# Earl-Nano-Stepper-Dual.net
KiCad netlist of a schematic drawn in EAGLE
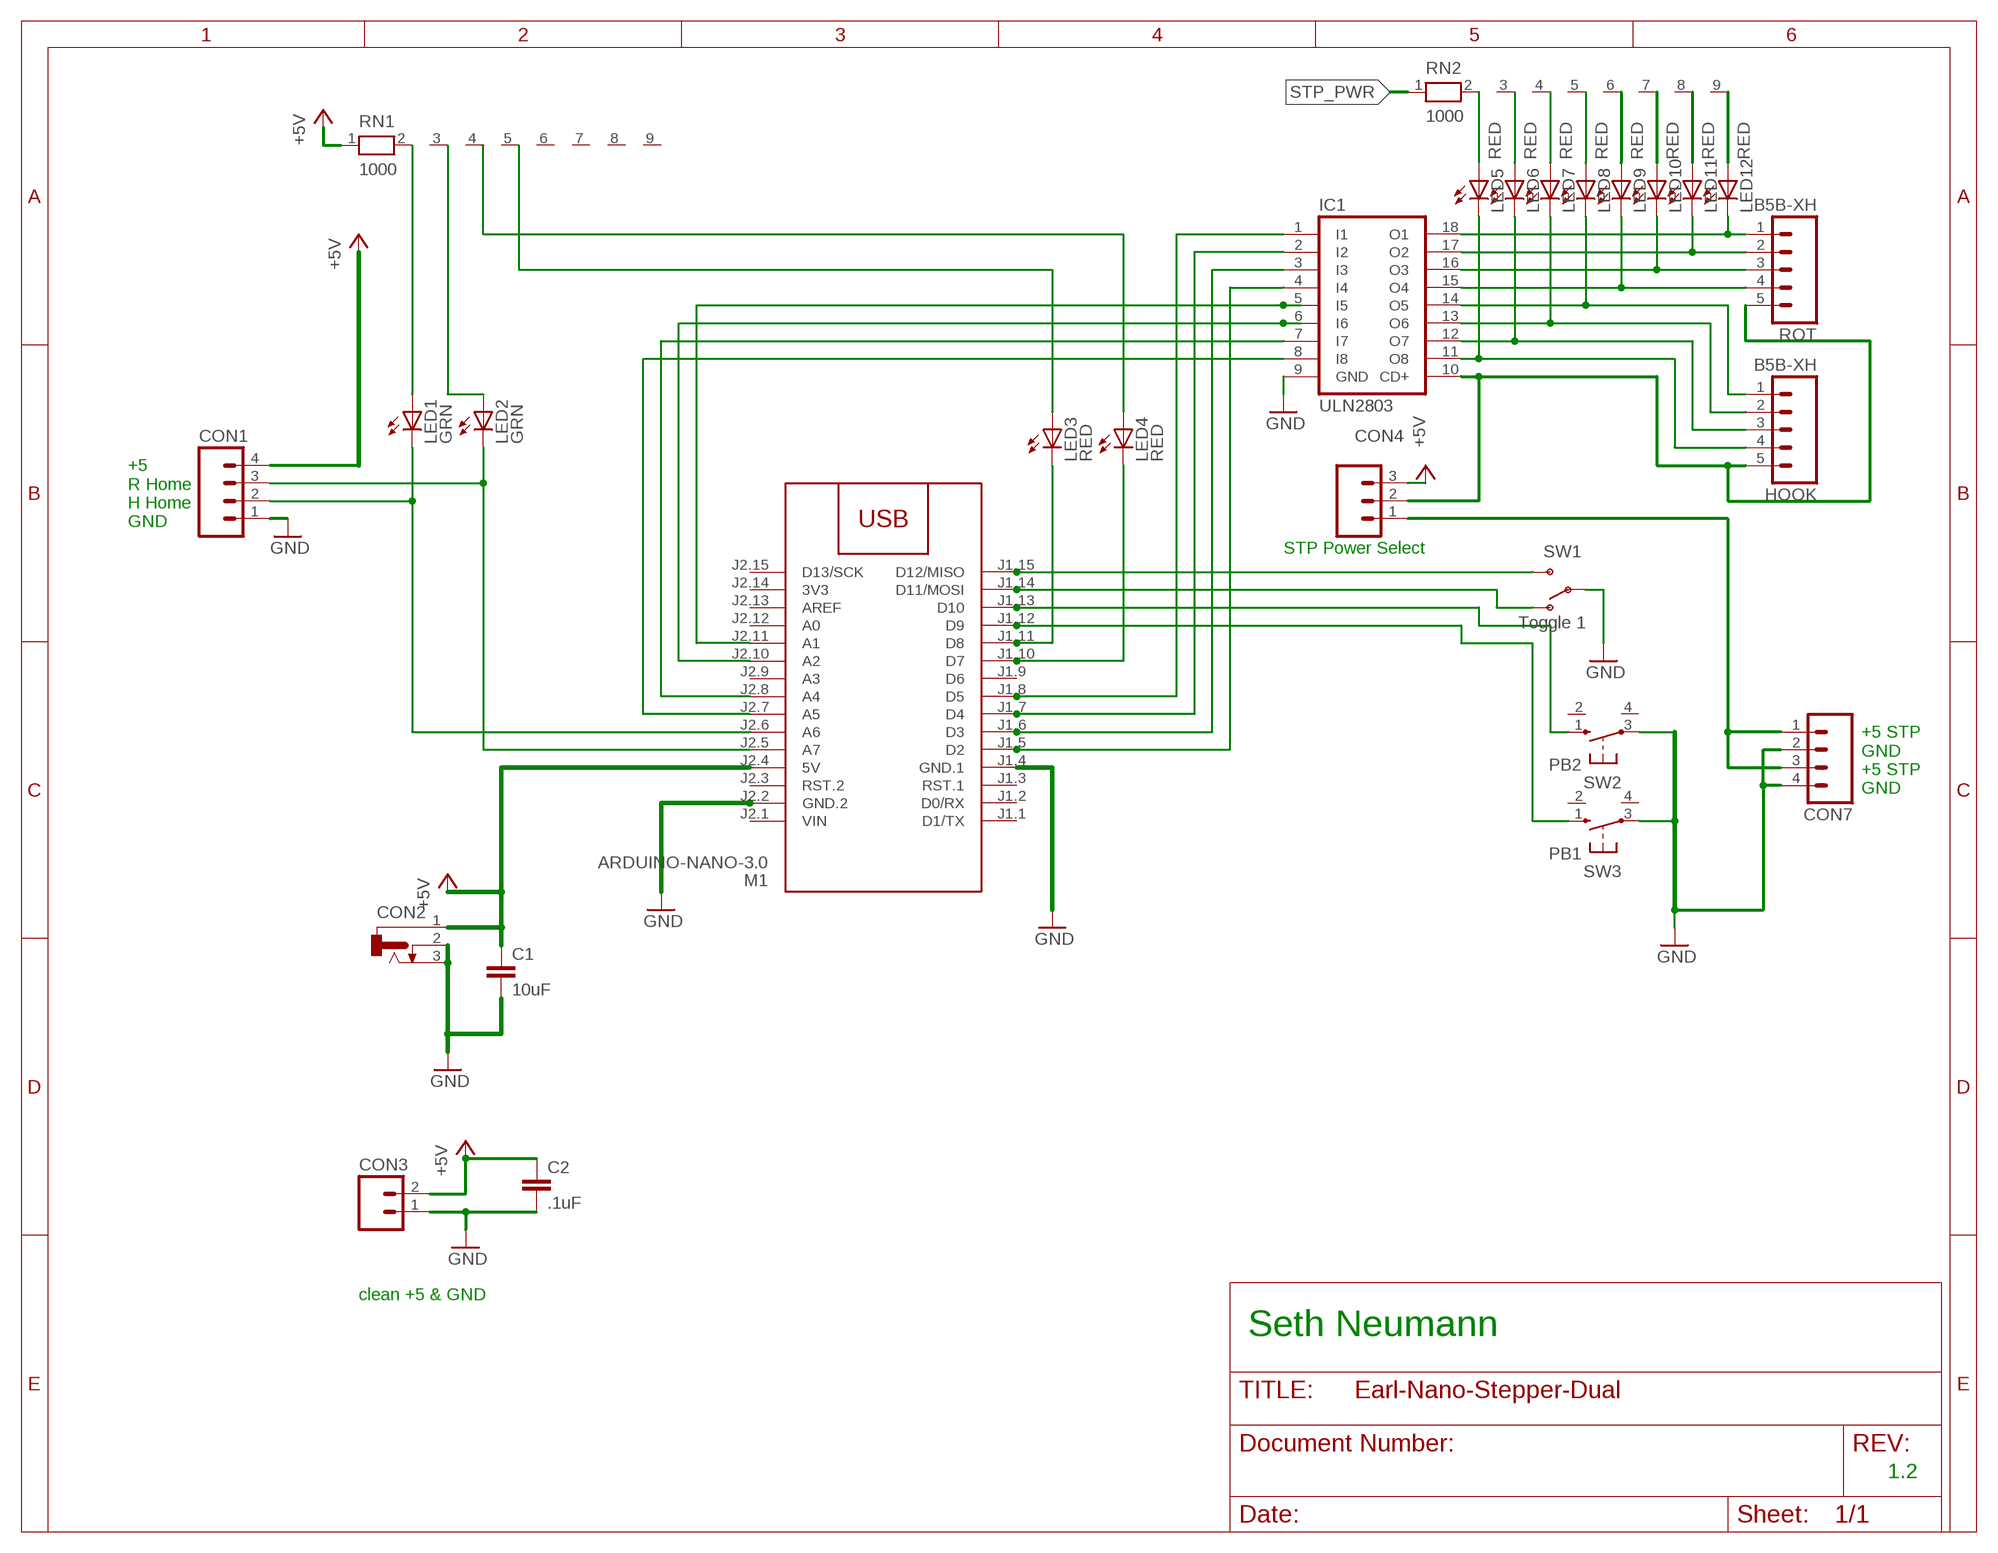
[diagram p0: schematic, sheet 1]

(export (version "E")
  (design (tool "Eeschema 10.0.6"))
  (components
    (comp (ref "C1")
      (value "10uF")
      (footprint "eagle-import:C5B3")
      (libsource (lib "eagle-import") (part "C5/3"))
    )
    (comp (ref "C2")
      (value ".1uF")
      (footprint "eagle-import:C5B3")
      (libsource (lib "eagle-import") (part "C5/3"))
    )
    (comp (ref "CON1")
      (value "CONNECTOR-M04LOCK")
      (footprint "eagle-import:1X04_LOCK")
      (libsource (lib "eagle-import") (part "CONNECTOR-M04LOCK"))
    )
    (comp (ref "CON2")
      (value "CONNECTOR-DC-POWER-RA")
      (footprint "eagle-import:DCJ0202")
      (libsource (lib "eagle-import") (part "CONNECTOR-DC-POWER-RA"))
    )
    (comp (ref "CON3")
      (value "CONNECTOR-M02350-LOCK")
      (footprint "eagle-import:1751248")
      (libsource (lib "eagle-import") (part "CONNECTOR-M02350-LOCK"))
    )
    (comp (ref "CON4")
      (value "CONNECTOR-M03254-LOCK")
      (footprint "eagle-import:3POL254")
      (libsource (lib "eagle-import") (part "CONNECTOR-M03254-LOCK"))
    )
    (comp (ref "CON7")
      (value "CONNECTOR-M04SCREW_LOCK")
      (footprint "eagle-import:SCREWTERMINAL-3.5MM-4_LOCK")
      (libsource (lib "eagle-import") (part "CONNECTOR-M04SCREW_LOCK"))
    )
    (comp (ref "HOOK")
      (value "B5B-XH")
      (footprint "eagle-import:1X05_LOCK")
      (libsource (lib "eagle-import") (part "CONNECTOR-M05LOCK"))
    )
    (comp (ref "IC1")
      (value "ULN2803")
      (footprint "eagle-import:DIL18")
      (libsource (lib "eagle-import") (part "ULN2803A"))
    )
    (comp (ref "LED1")
      (value "GRN")
      (footprint "eagle-import:LED3MM")
      (libsource (lib "eagle-import") (part "LEDLED3MM"))
    )
    (comp (ref "LED2")
      (value "GRN")
      (footprint "eagle-import:LED3MM")
      (libsource (lib "eagle-import") (part "LEDLED3MM"))
    )
    (comp (ref "LED3")
      (value "RED")
      (footprint "eagle-import:LED3MM")
      (libsource (lib "eagle-import") (part "LEDLED3MM"))
    )
    (comp (ref "LED4")
      (value "RED")
      (footprint "eagle-import:LED3MM")
      (libsource (lib "eagle-import") (part "LEDLED3MM"))
    )
    (comp (ref "LED5")
      (value "RED")
      (footprint "eagle-import:LED3MM")
      (libsource (lib "eagle-import") (part "LEDLED3MM"))
    )
    (comp (ref "LED6")
      (value "RED")
      (footprint "eagle-import:LED3MM")
      (libsource (lib "eagle-import") (part "LEDLED3MM"))
    )
    (comp (ref "LED7")
      (value "RED")
      (footprint "eagle-import:LED3MM")
      (libsource (lib "eagle-import") (part "LEDLED3MM"))
    )
    (comp (ref "LED8")
      (value "RED")
      (footprint "eagle-import:LED3MM")
      (libsource (lib "eagle-import") (part "LEDLED3MM"))
    )
    (comp (ref "LED9")
      (value "RED")
      (footprint "eagle-import:LED3MM")
      (libsource (lib "eagle-import") (part "LEDLED3MM"))
    )
    (comp (ref "LED10")
      (value "RED")
      (footprint "eagle-import:LED3MM")
      (libsource (lib "eagle-import") (part "LEDLED3MM"))
    )
    (comp (ref "LED11")
      (value "RED")
      (footprint "eagle-import:LED3MM")
      (libsource (lib "eagle-import") (part "LEDLED3MM"))
    )
    (comp (ref "LED12")
      (value "RED")
      (footprint "eagle-import:LED3MM")
      (libsource (lib "eagle-import") (part "LEDLED3MM"))
    )
    (comp (ref "M1")
      (value "ARDUINO-NANO-3.0")
      (footprint "eagle-import:ARDUINO-NANO-3.0")
      (libsource (lib "eagle-import") (part "ARDUINO-NANO-3.0"))
    )
    (comp (ref "RN1")
      (value "1000")
      (footprint "eagle-import:RN-9")
      (libsource (lib "eagle-import") (part "RN08"))
    )
    (comp (ref "RN2")
      (value "1000")
      (footprint "eagle-import:RN-9")
      (libsource (lib "eagle-import") (part "RN08"))
    )
    (comp (ref "ROT")
      (value "B5B-XH")
      (footprint "eagle-import:1X05_LOCK")
      (libsource (lib "eagle-import") (part "CONNECTOR-M05LOCK"))
    )
    (comp (ref "SW1")
      (value "Toggle 1")
      (footprint "eagle-import:SWITCH-SPDT-508")
      (libsource (lib "eagle-import") (part "SWITCH-SPSTPTH-508"))
    )
    (comp (ref "SW2")
      (value "PB2")
      (footprint "eagle-import:4P-PTH-6.0X6.0X5.0H")
      (libsource (lib "eagle-import") (part "SWITCH-(ON)SMALLPADS"))
    )
    (comp (ref "SW3")
      (value "PB1")
      (footprint "eagle-import:4P-PTH-6.0X6.0X5.0H")
      (libsource (lib "eagle-import") (part "SWITCH-(ON)SMALLPADS"))
    )
  )
  (nets
    (net (code "1") (name "+5V") (class "Default")
      (node (ref "C1") (pin "1") (pinfunction "1_1") (pintype "passive"))
      (node (ref "C2") (pin "1") (pinfunction "1_1") (pintype "passive"))
      (node (ref "CON1") (pin "4") (pinfunction "4_4") (pintype "passive"))
      (node (ref "CON2") (pin "1") (pinfunction "1_1") (pintype "passive"))
      (node (ref "CON3") (pin "2") (pinfunction "B_2") (pintype "passive"))
      (node (ref "CON4") (pin "3") (pinfunction "3_3") (pintype "passive"))
      (node (ref "M1") (pin "J2.4") (pinfunction "5V_J2.4") (pintype "power_in"))
      (node (ref "RN1") (pin "1") (pinfunction "1_1") (pintype "passive"))
    )
    (net (code "2") (name "/3V3") (class "Default")
      (node (ref "M1") (pin "J2.14") (pinfunction "3V3_J2.14") (pintype "power_in"))
    )
    (net (code "3") (name "/VIN") (class "Default")
      (node (ref "M1") (pin "J2.1") (pinfunction "VIN_J2.1") (pintype "power_in"))
    )
    (net (code "4") (name "GND") (class "Default")
      (node (ref "C1") (pin "2") (pinfunction "2_2") (pintype "passive"))
      (node (ref "C2") (pin "2") (pinfunction "2_2") (pintype "passive"))
      (node (ref "CON1") (pin "1") (pinfunction "1_1") (pintype "passive"))
      (node (ref "CON2") (pin "2") (pinfunction "2_2") (pintype "passive"))
      (node (ref "CON2") (pin "3") (pinfunction "3_3") (pintype "passive"))
      (node (ref "CON3") (pin "1") (pinfunction "A_1") (pintype "passive"))
      (node (ref "CON7") (pin "2") (pinfunction "2_2") (pintype "passive"))
      (node (ref "CON7") (pin "4") (pinfunction "4_4") (pintype "passive"))
      (node (ref "IC1") (pin "9") (pinfunction "GND_9") (pintype "power_in"))
      (node (ref "M1") (pin "J1.4") (pinfunction "GND.1_J1.4") (pintype "power_in"))
      (node (ref "M1") (pin "J2.2") (pinfunction "GND.2_J2.2") (pintype "power_in"))
      (node (ref "SW1") (pin "2") (pinfunction "P_2") (pintype "passive"))
      (node (ref "SW2") (pin "3") (pinfunction "P_3") (pintype "passive"))
      (node (ref "SW3") (pin "3") (pinfunction "P_3") (pintype "passive"))
    )
    (net (code "5") (name "Net-(CON4-Pad1)") (class "Default")
      (node (ref "CON4") (pin "1") (pinfunction "1_1") (pintype "passive"))
      (node (ref "CON7") (pin "1") (pinfunction "1_1") (pintype "passive"))
      (node (ref "CON7") (pin "3") (pinfunction "3_3") (pintype "passive"))
    )
    (net (code "6") (name "Net-(IC1-I1)") (class "Default")
      (node (ref "IC1") (pin "1") (pinfunction "I1_1") (pintype "input"))
      (node (ref "M1") (pin "J1.8") (pinfunction "D5_J1.8") (pintype "bidirectional"))
    )
    (net (code "7") (name "Net-(IC1-I2)") (class "Default")
      (node (ref "IC1") (pin "2") (pinfunction "I2_2") (pintype "input"))
      (node (ref "M1") (pin "J1.7") (pinfunction "D4_J1.7") (pintype "bidirectional"))
    )
    (net (code "8") (name "Net-(IC1-I3)") (class "Default")
      (node (ref "IC1") (pin "3") (pinfunction "I3_3") (pintype "input"))
      (node (ref "M1") (pin "J1.6") (pinfunction "D3_J1.6") (pintype "bidirectional"))
    )
    (net (code "9") (name "Net-(IC1-I4)") (class "Default")
      (node (ref "IC1") (pin "4") (pinfunction "I4_4") (pintype "input"))
      (node (ref "M1") (pin "J1.5") (pinfunction "D2_J1.5") (pintype "bidirectional"))
    )
    (net (code "10") (name "Net-(IC1-I5)") (class "Default")
      (node (ref "IC1") (pin "5") (pinfunction "I5_5") (pintype "input"))
      (node (ref "M1") (pin "J2.11") (pinfunction "A1_J2.11") (pintype "bidirectional"))
    )
    (net (code "11") (name "Net-(IC1-I6)") (class "Default")
      (node (ref "IC1") (pin "6") (pinfunction "I6_6") (pintype "input"))
      (node (ref "M1") (pin "J2.10") (pinfunction "A2_J2.10") (pintype "bidirectional"))
    )
    (net (code "12") (name "Net-(IC1-I7)") (class "Default")
      (node (ref "IC1") (pin "7") (pinfunction "I7_7") (pintype "input"))
      (node (ref "M1") (pin "J2.8") (pinfunction "A4_J2.8") (pintype "bidirectional"))
    )
    (net (code "13") (name "Net-(IC1-I8)") (class "Default")
      (node (ref "IC1") (pin "8") (pinfunction "I8_8") (pintype "input"))
      (node (ref "M1") (pin "J2.7") (pinfunction "A5_J2.7") (pintype "bidirectional"))
    )
    (net (code "14") (name "Net-(IC1-O1)") (class "Default")
      (node (ref "IC1") (pin "18") (pinfunction "O1_18") (pintype "open_collector"))
      (node (ref "LED12") (pin "K") (pinfunction "C_K") (pintype "passive"))
      (node (ref "ROT") (pin "1") (pinfunction "1_1") (pintype "passive"))
    )
    (net (code "15") (name "Net-(IC1-O2)") (class "Default")
      (node (ref "IC1") (pin "17") (pinfunction "O2_17") (pintype "open_collector"))
      (node (ref "LED11") (pin "K") (pinfunction "C_K") (pintype "passive"))
      (node (ref "ROT") (pin "2") (pinfunction "2_2") (pintype "passive"))
    )
    (net (code "16") (name "Net-(IC1-O3)") (class "Default")
      (node (ref "IC1") (pin "16") (pinfunction "O3_16") (pintype "open_collector"))
      (node (ref "LED10") (pin "K") (pinfunction "C_K") (pintype "passive"))
      (node (ref "ROT") (pin "3") (pinfunction "3_3") (pintype "passive"))
    )
    (net (code "17") (name "Net-(IC1-O4)") (class "Default")
      (node (ref "IC1") (pin "15") (pinfunction "O4_15") (pintype "open_collector"))
      (node (ref "LED9") (pin "K") (pinfunction "C_K") (pintype "passive"))
      (node (ref "ROT") (pin "4") (pinfunction "4_4") (pintype "passive"))
    )
    (net (code "18") (name "Net-(IC1-O5)") (class "Default")
      (node (ref "HOOK") (pin "1") (pinfunction "1_1") (pintype "passive"))
      (node (ref "IC1") (pin "14") (pinfunction "O5_14") (pintype "open_collector"))
      (node (ref "LED8") (pin "K") (pinfunction "C_K") (pintype "passive"))
    )
    (net (code "19") (name "Net-(IC1-O6)") (class "Default")
      (node (ref "HOOK") (pin "2") (pinfunction "2_2") (pintype "passive"))
      (node (ref "IC1") (pin "13") (pinfunction "O6_13") (pintype "open_collector"))
      (node (ref "LED7") (pin "K") (pinfunction "C_K") (pintype "passive"))
    )
    (net (code "20") (name "Net-(IC1-O7)") (class "Default")
      (node (ref "HOOK") (pin "3") (pinfunction "3_3") (pintype "passive"))
      (node (ref "IC1") (pin "12") (pinfunction "O7_12") (pintype "open_collector"))
      (node (ref "LED6") (pin "K") (pinfunction "C_K") (pintype "passive"))
    )
    (net (code "21") (name "Net-(IC1-O8)") (class "Default")
      (node (ref "HOOK") (pin "4") (pinfunction "4_4") (pintype "passive"))
      (node (ref "IC1") (pin "11") (pinfunction "O8_11") (pintype "open_collector"))
      (node (ref "LED5") (pin "K") (pinfunction "C_K") (pintype "passive"))
    )
    (net (code "22") (name "Net-(LED1-C)") (class "Default")
      (node (ref "CON1") (pin "2") (pinfunction "2_2") (pintype "passive"))
      (node (ref "LED1") (pin "K") (pinfunction "C_K") (pintype "passive"))
      (node (ref "M1") (pin "J2.6") (pinfunction "A6_J2.6") (pintype "bidirectional"))
    )
    (net (code "23") (name "Net-(LED1-PadA)") (class "Default")
      (node (ref "LED1") (pin "A") (pinfunction "A_A") (pintype "passive"))
      (node (ref "RN1") (pin "2") (pinfunction "2_2") (pintype "passive"))
    )
    (net (code "24") (name "Net-(LED2-C)") (class "Default")
      (node (ref "CON1") (pin "3") (pinfunction "3_3") (pintype "passive"))
      (node (ref "LED2") (pin "K") (pinfunction "C_K") (pintype "passive"))
      (node (ref "M1") (pin "J2.5") (pinfunction "A7_J2.5") (pintype "bidirectional"))
    )
    (net (code "25") (name "Net-(LED2-PadA)") (class "Default")
      (node (ref "LED2") (pin "A") (pinfunction "A_A") (pintype "passive"))
      (node (ref "RN1") (pin "3") (pinfunction "3_3") (pintype "passive"))
    )
    (net (code "26") (name "Net-(LED3-C)") (class "Default")
      (node (ref "LED3") (pin "K") (pinfunction "C_K") (pintype "passive"))
      (node (ref "M1") (pin "J1.11") (pinfunction "D8_J1.11") (pintype "bidirectional"))
    )
    (net (code "27") (name "Net-(LED3-PadA)") (class "Default")
      (node (ref "LED3") (pin "A") (pinfunction "A_A") (pintype "passive"))
      (node (ref "RN1") (pin "5") (pinfunction "5_5") (pintype "passive"))
    )
    (net (code "28") (name "Net-(LED4-C)") (class "Default")
      (node (ref "LED4") (pin "K") (pinfunction "C_K") (pintype "passive"))
      (node (ref "M1") (pin "J1.10") (pinfunction "D7_J1.10") (pintype "bidirectional"))
    )
    (net (code "29") (name "Net-(LED4-PadA)") (class "Default")
      (node (ref "LED4") (pin "A") (pinfunction "A_A") (pintype "passive"))
      (node (ref "RN1") (pin "4") (pinfunction "4_4") (pintype "passive"))
    )
    (net (code "30") (name "Net-(LED5-PadA)") (class "Default")
      (node (ref "LED5") (pin "A") (pinfunction "A_A") (pintype "passive"))
      (node (ref "RN2") (pin "2") (pinfunction "2_2") (pintype "passive"))
    )
    (net (code "31") (name "Net-(LED6-PadA)") (class "Default")
      (node (ref "LED6") (pin "A") (pinfunction "A_A") (pintype "passive"))
      (node (ref "RN2") (pin "3") (pinfunction "3_3") (pintype "passive"))
    )
    (net (code "32") (name "Net-(LED7-PadA)") (class "Default")
      (node (ref "LED7") (pin "A") (pinfunction "A_A") (pintype "passive"))
      (node (ref "RN2") (pin "4") (pinfunction "4_4") (pintype "passive"))
    )
    (net (code "33") (name "Net-(LED8-PadA)") (class "Default")
      (node (ref "LED8") (pin "A") (pinfunction "A_A") (pintype "passive"))
      (node (ref "RN2") (pin "5") (pinfunction "5_5") (pintype "passive"))
    )
    (net (code "34") (name "Net-(LED9-PadA)") (class "Default")
      (node (ref "LED9") (pin "A") (pinfunction "A_A") (pintype "passive"))
      (node (ref "RN2") (pin "6") (pinfunction "6_6") (pintype "passive"))
    )
    (net (code "35") (name "Net-(LED10-PadA)") (class "Default")
      (node (ref "LED10") (pin "A") (pinfunction "A_A") (pintype "passive"))
      (node (ref "RN2") (pin "7") (pinfunction "7_7") (pintype "passive"))
    )
    (net (code "36") (name "Net-(LED11-PadA)") (class "Default")
      (node (ref "LED11") (pin "A") (pinfunction "A_A") (pintype "passive"))
      (node (ref "RN2") (pin "8") (pinfunction "8_8") (pintype "passive"))
    )
    (net (code "37") (name "Net-(LED12-PadA)") (class "Default")
      (node (ref "LED12") (pin "A") (pinfunction "A_A") (pintype "passive"))
      (node (ref "RN2") (pin "9") (pinfunction "9_9") (pintype "passive"))
    )
    (net (code "38") (name "Net-(M1-D9)") (class "Default")
      (node (ref "M1") (pin "J1.12") (pinfunction "D9_J1.12") (pintype "bidirectional"))
      (node (ref "SW3") (pin "1") (pinfunction "S_1") (pintype "passive"))
    )
    (net (code "39") (name "Net-(M1-D10)") (class "Default")
      (node (ref "M1") (pin "J1.13") (pinfunction "D10_J1.13") (pintype "bidirectional"))
      (node (ref "SW2") (pin "1") (pinfunction "S_1") (pintype "passive"))
    )
    (net (code "40") (name "Net-(M1-D11{slash}MOSI)") (class "Default")
      (node (ref "M1") (pin "J1.14") (pinfunction "D11/MOSI_J1.14") (pintype "bidirectional"))
      (node (ref "SW1") (pin "1") (pinfunction "O_1") (pintype "passive"))
    )
    (net (code "41") (name "Net-(M1-D12{slash}MISO)") (class "Default")
      (node (ref "M1") (pin "J1.15") (pinfunction "D12/MISO_J1.15") (pintype "bidirectional"))
      (node (ref "SW1") (pin "3") (pinfunction "S_3") (pintype "passive"))
    )
    (net (code "42") (name "STP_PWR") (class "Default")
      (node (ref "CON4") (pin "2") (pinfunction "2_2") (pintype "passive"))
      (node (ref "HOOK") (pin "5") (pinfunction "5_5") (pintype "passive"))
      (node (ref "IC1") (pin "10") (pinfunction "CD+_10") (pintype "passive"))
      (node (ref "RN2") (pin "1") (pinfunction "1_1") (pintype "passive"))
      (node (ref "ROT") (pin "5") (pinfunction "5_5") (pintype "passive"))
    )
    (net (code "43") (name "unconnected-(M1-A0-PadJ2.12)") (class "Default")
      (node (ref "M1") (pin "J2.12") (pinfunction "A0_J2.12") (pintype "bidirectional"))
    )
    (net (code "44") (name "unconnected-(M1-A3-PadJ2.9)") (class "Default")
      (node (ref "M1") (pin "J2.9") (pinfunction "A3_J2.9") (pintype "bidirectional"))
    )
    (net (code "45") (name "unconnected-(M1-AREF-PadJ2.13)") (class "Default")
      (node (ref "M1") (pin "J2.13") (pinfunction "AREF_J2.13") (pintype "bidirectional"))
    )
    (net (code "46") (name "unconnected-(M1-D0{slash}RX-PadJ1.2)") (class "Default")
      (node (ref "M1") (pin "J1.2") (pinfunction "D0/RX_J1.2") (pintype "bidirectional"))
    )
    (net (code "47") (name "unconnected-(M1-D1{slash}TX-PadJ1.1)") (class "Default")
      (node (ref "M1") (pin "J1.1") (pinfunction "D1/TX_J1.1") (pintype "bidirectional"))
    )
    (net (code "48") (name "unconnected-(M1-D6-PadJ1.9)") (class "Default")
      (node (ref "M1") (pin "J1.9") (pinfunction "D6_J1.9") (pintype "bidirectional"))
    )
    (net (code "49") (name "unconnected-(M1-D13{slash}SCK-PadJ2.15)") (class "Default")
      (node (ref "M1") (pin "J2.15") (pinfunction "D13/SCK_J2.15") (pintype "bidirectional"))
    )
    (net (code "50") (name "unconnected-(M1-RST.1-PadJ1.3)") (class "Default")
      (node (ref "M1") (pin "J1.3") (pinfunction "RST.1_J1.3") (pintype "bidirectional"))
    )
    (net (code "51") (name "unconnected-(M1-RST.2-PadJ2.3)") (class "Default")
      (node (ref "M1") (pin "J2.3") (pinfunction "RST.2_J2.3") (pintype "bidirectional"))
    )
    (net (code "52") (name "unconnected-(RN1-Pad6)") (class "Default")
      (node (ref "RN1") (pin "6") (pinfunction "6_6") (pintype "passive"))
    )
    (net (code "53") (name "unconnected-(RN1-Pad7)") (class "Default")
      (node (ref "RN1") (pin "7") (pinfunction "7_7") (pintype "passive"))
    )
    (net (code "54") (name "unconnected-(RN1-Pad8)") (class "Default")
      (node (ref "RN1") (pin "8") (pinfunction "8_8") (pintype "passive"))
    )
    (net (code "55") (name "unconnected-(RN1-Pad9)") (class "Default")
      (node (ref "RN1") (pin "9") (pinfunction "9_9") (pintype "passive"))
    )
    (net (code "56") (name "unconnected-(SW2-P1-Pad4)") (class "Default")
      (node (ref "SW2") (pin "4") (pinfunction "P1_4") (pintype "passive"))
    )
    (net (code "57") (name "unconnected-(SW2-S1-Pad2)") (class "Default")
      (node (ref "SW2") (pin "2") (pinfunction "S1_2") (pintype "passive"))
    )
    (net (code "58") (name "unconnected-(SW3-P1-Pad4)") (class "Default")
      (node (ref "SW3") (pin "4") (pinfunction "P1_4") (pintype "passive"))
    )
    (net (code "59") (name "unconnected-(SW3-S1-Pad2)") (class "Default")
      (node (ref "SW3") (pin "2") (pinfunction "S1_2") (pintype "passive"))
    )
  )
)
